# MAX31855-Breakout-Board.net
KiCad netlist of a schematic drawn in EAGLE
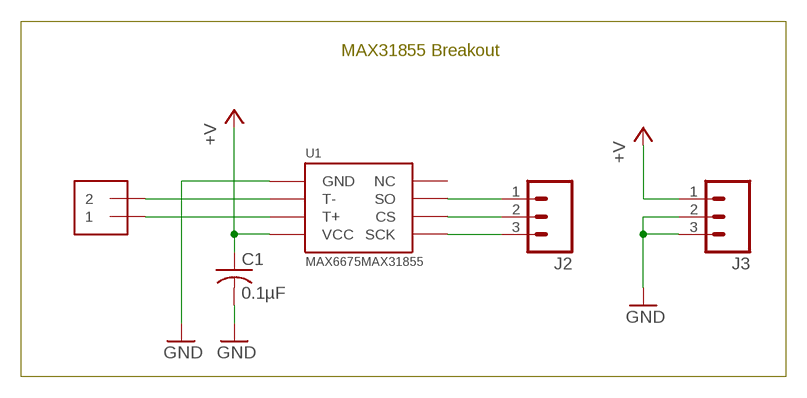
[diagram p0: schematic, sheet 1]

(export (version "E")
  (design (tool "Eeschema 10.0.6"))
  (components
    (comp (ref "C1")
      (value "0.1µF")
      (footprint "eagle-import:C0603")
      (libsource (lib "eagle-import") (part "C-USC0603"))
    )
    (comp (ref "J2")
      (value "M031X03_NO_SILK")
      (footprint "eagle-import:1X03_NO_SILK")
      (libsource (lib "eagle-import") (part "M031X03_NO_SILK"))
    )
    (comp (ref "J3")
      (value "M031X03_NO_SILK")
      (footprint "eagle-import:1X03_NO_SILK")
      (libsource (lib "eagle-import") (part "M031X03_NO_SILK"))
    )
    (comp (ref "J4")
      (value "1X2-3.5MM")
      (footprint "eagle-import:1X2-3.5MM")
      (libsource (lib "eagle-import") (part "1X2-3.5MM"))
    )
    (comp (ref "U1")
      (value "MAX6675MAX31855")
      (footprint "eagle-import:SOIC-8")
      (libsource (lib "eagle-import") (part "MAX6675MAX31855"))
    )
  )
  (nets
    (net (code "1") (name "+V") (class "Default")
      (node (ref "C1") (pin "1") (pinfunction "1_1") (pintype "passive"))
      (node (ref "J3") (pin "1") (pinfunction "1_1") (pintype "passive"))
      (node (ref "U1") (pin "VCC") (pinfunction "VCC_VCC") (pintype "bidirectional"))
    )
    (net (code "2") (name "GND") (class "Default")
      (node (ref "C1") (pin "2") (pinfunction "2_2") (pintype "passive"))
      (node (ref "J3") (pin "2") (pinfunction "2_2") (pintype "passive"))
      (node (ref "J3") (pin "3") (pinfunction "3_3") (pintype "passive"))
      (node (ref "U1") (pin "GND") (pinfunction "GND_GND") (pintype "bidirectional"))
    )
    (net (code "3") (name "Net-(J2-Pad1)") (class "Default")
      (node (ref "J2") (pin "1") (pinfunction "1_1") (pintype "passive"))
      (node (ref "U1") (pin "SO") (pinfunction "SO_SO") (pintype "bidirectional"))
    )
    (net (code "4") (name "Net-(J2-Pad2)") (class "Default")
      (node (ref "J2") (pin "2") (pinfunction "2_2") (pintype "passive"))
      (node (ref "U1") (pin "CS") (pinfunction "CS_CS") (pintype "bidirectional"))
    )
    (net (code "5") (name "Net-(J2-Pad3)") (class "Default")
      (node (ref "J2") (pin "3") (pinfunction "3_3") (pintype "passive"))
      (node (ref "U1") (pin "SCK") (pinfunction "SCK_SCK") (pintype "bidirectional"))
    )
    (net (code "6") (name "Net-(J4-Pad1)") (class "Default")
      (node (ref "J4") (pin "1") (pinfunction "1_1") (pintype "passive"))
      (node (ref "U1") (pin "T+") (pinfunction "T+_T+") (pintype "bidirectional"))
    )
    (net (code "7") (name "Net-(J4-Pad2)") (class "Default")
      (node (ref "J4") (pin "2") (pinfunction "2_2") (pintype "passive"))
      (node (ref "U1") (pin "T-") (pinfunction "T-_T-") (pintype "bidirectional"))
    )
    (net (code "8") (name "unconnected-(U1-PadNC)") (class "Default")
      (node (ref "U1") (pin "NC") (pinfunction "NC_NC") (pintype "no_connect"))
    )
  )
)
